# OSC.net
KiCad netlist of a schematic drawn in Altium Designer
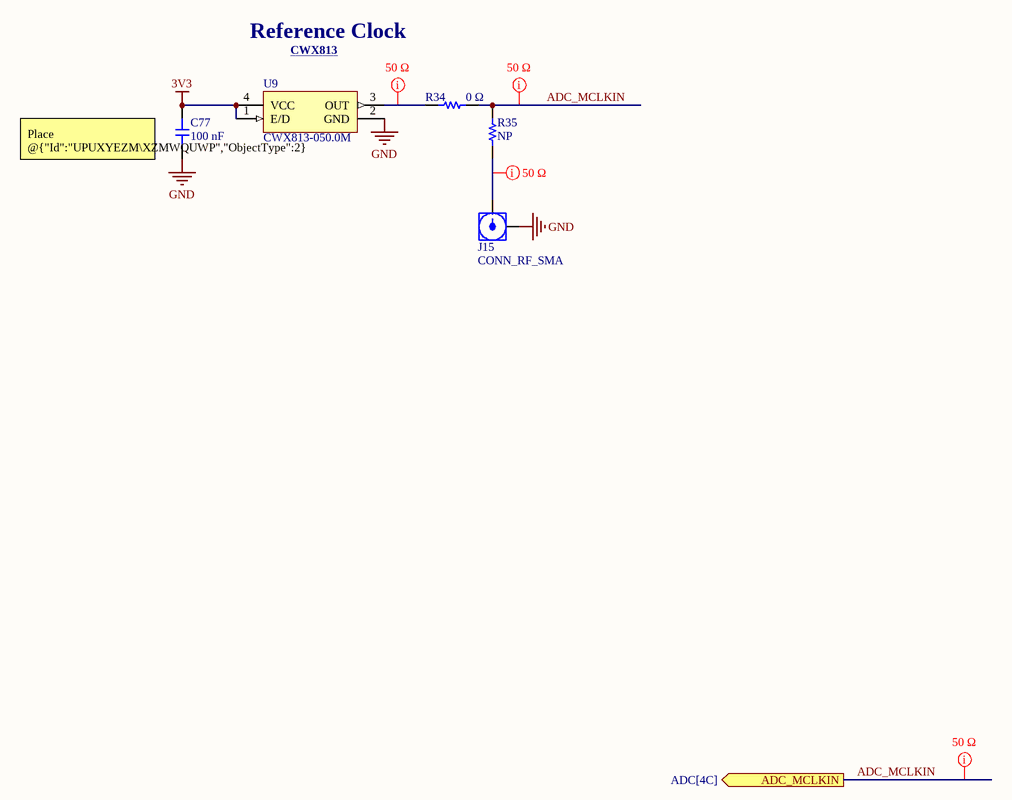
[diagram p0: OSC.SchDoc]

(export (version "E")
  (design (tool "Eeschema 10.0.6"))
  (components
    (comp (ref "C77")
      (value "100 nF")
      (footprint "CAP_0402")
      (description "Ceramic Capacitor, Ceramic, 50V, 10% +Tol, 10% -Tol, X7R, 15% TC, 0.1uF, Surface Mount, 0402")
      (fields
        (field (name "MANUFACTURER") "Yageo")
        (field (name "MANUFACTURER PART NUMBER") "CC0402KPX7R9BB104")
      )
      (libsource (lib "Titan") (part "CAP"))
    )
    (comp (ref "J15")
      (value "CONN_RF_SMA")
      (footprint "142-0701-801")
      (description "RF / Coaxial Connector, SMA Coaxial, Straight Jack, Solder, 50 ohm, Beryllium Copper")
      (fields
        (field (name "MANUFACTURER") "Cinch Connectivity Solutions Johnson")
        (field (name "MANUFACTURER PART NUMBER") "142-0701-801")
      )
      (libsource (lib "Titan") (part "CONN_RF_SMA"))
    )
    (comp (ref "R34")
      (value "0 Ω")
      (footprint "RES_0402")
      (description "GENERAL PURPOSE CHIP RESISTOR Metal Glaze/thick Film, 0.0625W, 0ohm, Surface Mount, 0402")
      (fields
        (field (name "MANUFACTURER") "Yageo")
        (field (name "MANUFACTURER PART NUMBER") "RC0402FR-070RL")
      )
      (libsource (lib "Titan") (part "RES"))
    )
    (comp (ref "R35")
      (value "NP")
      (footprint "RES_0402")
      (description "Resistor SMD Generic")
      (libsource (lib "Titan") (part "RES"))
    )
    (comp (ref "U9")
      (value "CWX813-050.0M")
      (footprint "CWX8XX")
      (description "LVCMOS Output Clock Oscillator, 50MHz Nom")
      (fields (field (name "MANUFACTURER") "Connor-Winfield"))
      (libsource (lib "Titan") (part "CWX813-050.0M"))
    )
  )
  (nets
    (net (code "1") (name "/ADC_MCLKIN") (class "Default")
      (node (ref "R34") (pin "2") (pintype "passive"))
      (node (ref "R35") (pin "2") (pintype "passive"))
    )
    (net (code "2") (name "3V3") (class "Default")
      (node (ref "C77") (pin "2") (pintype "passive"))
      (node (ref "U9") (pin "1") (pinfunction "E/D_1") (pintype "input"))
      (node (ref "U9") (pin "4") (pinfunction "VCC_4") (pintype "power_in"))
    )
    (net (code "3") (name "GND") (class "Default")
      (node (ref "C77") (pin "1") (pintype "passive"))
      (node (ref "J15") (pin "2") (pintype "passive"))
      (node (ref "U9") (pin "2") (pinfunction "GND_2") (pintype "power_in"))
    )
    (net (code "4") (name "Net-(J15-Pad1)") (class "Default")
      (node (ref "J15") (pin "1") (pintype "passive"))
      (node (ref "R35") (pin "1") (pintype "passive"))
    )
    (net (code "5") (name "Net-(U9-OUT)") (class "Default")
      (node (ref "R34") (pin "1") (pintype "passive"))
      (node (ref "U9") (pin "3") (pinfunction "OUT_3") (pintype "output"))
    )
  )
)
